# control_board.net
KiCad netlist of a schematic drawn in EAGLE
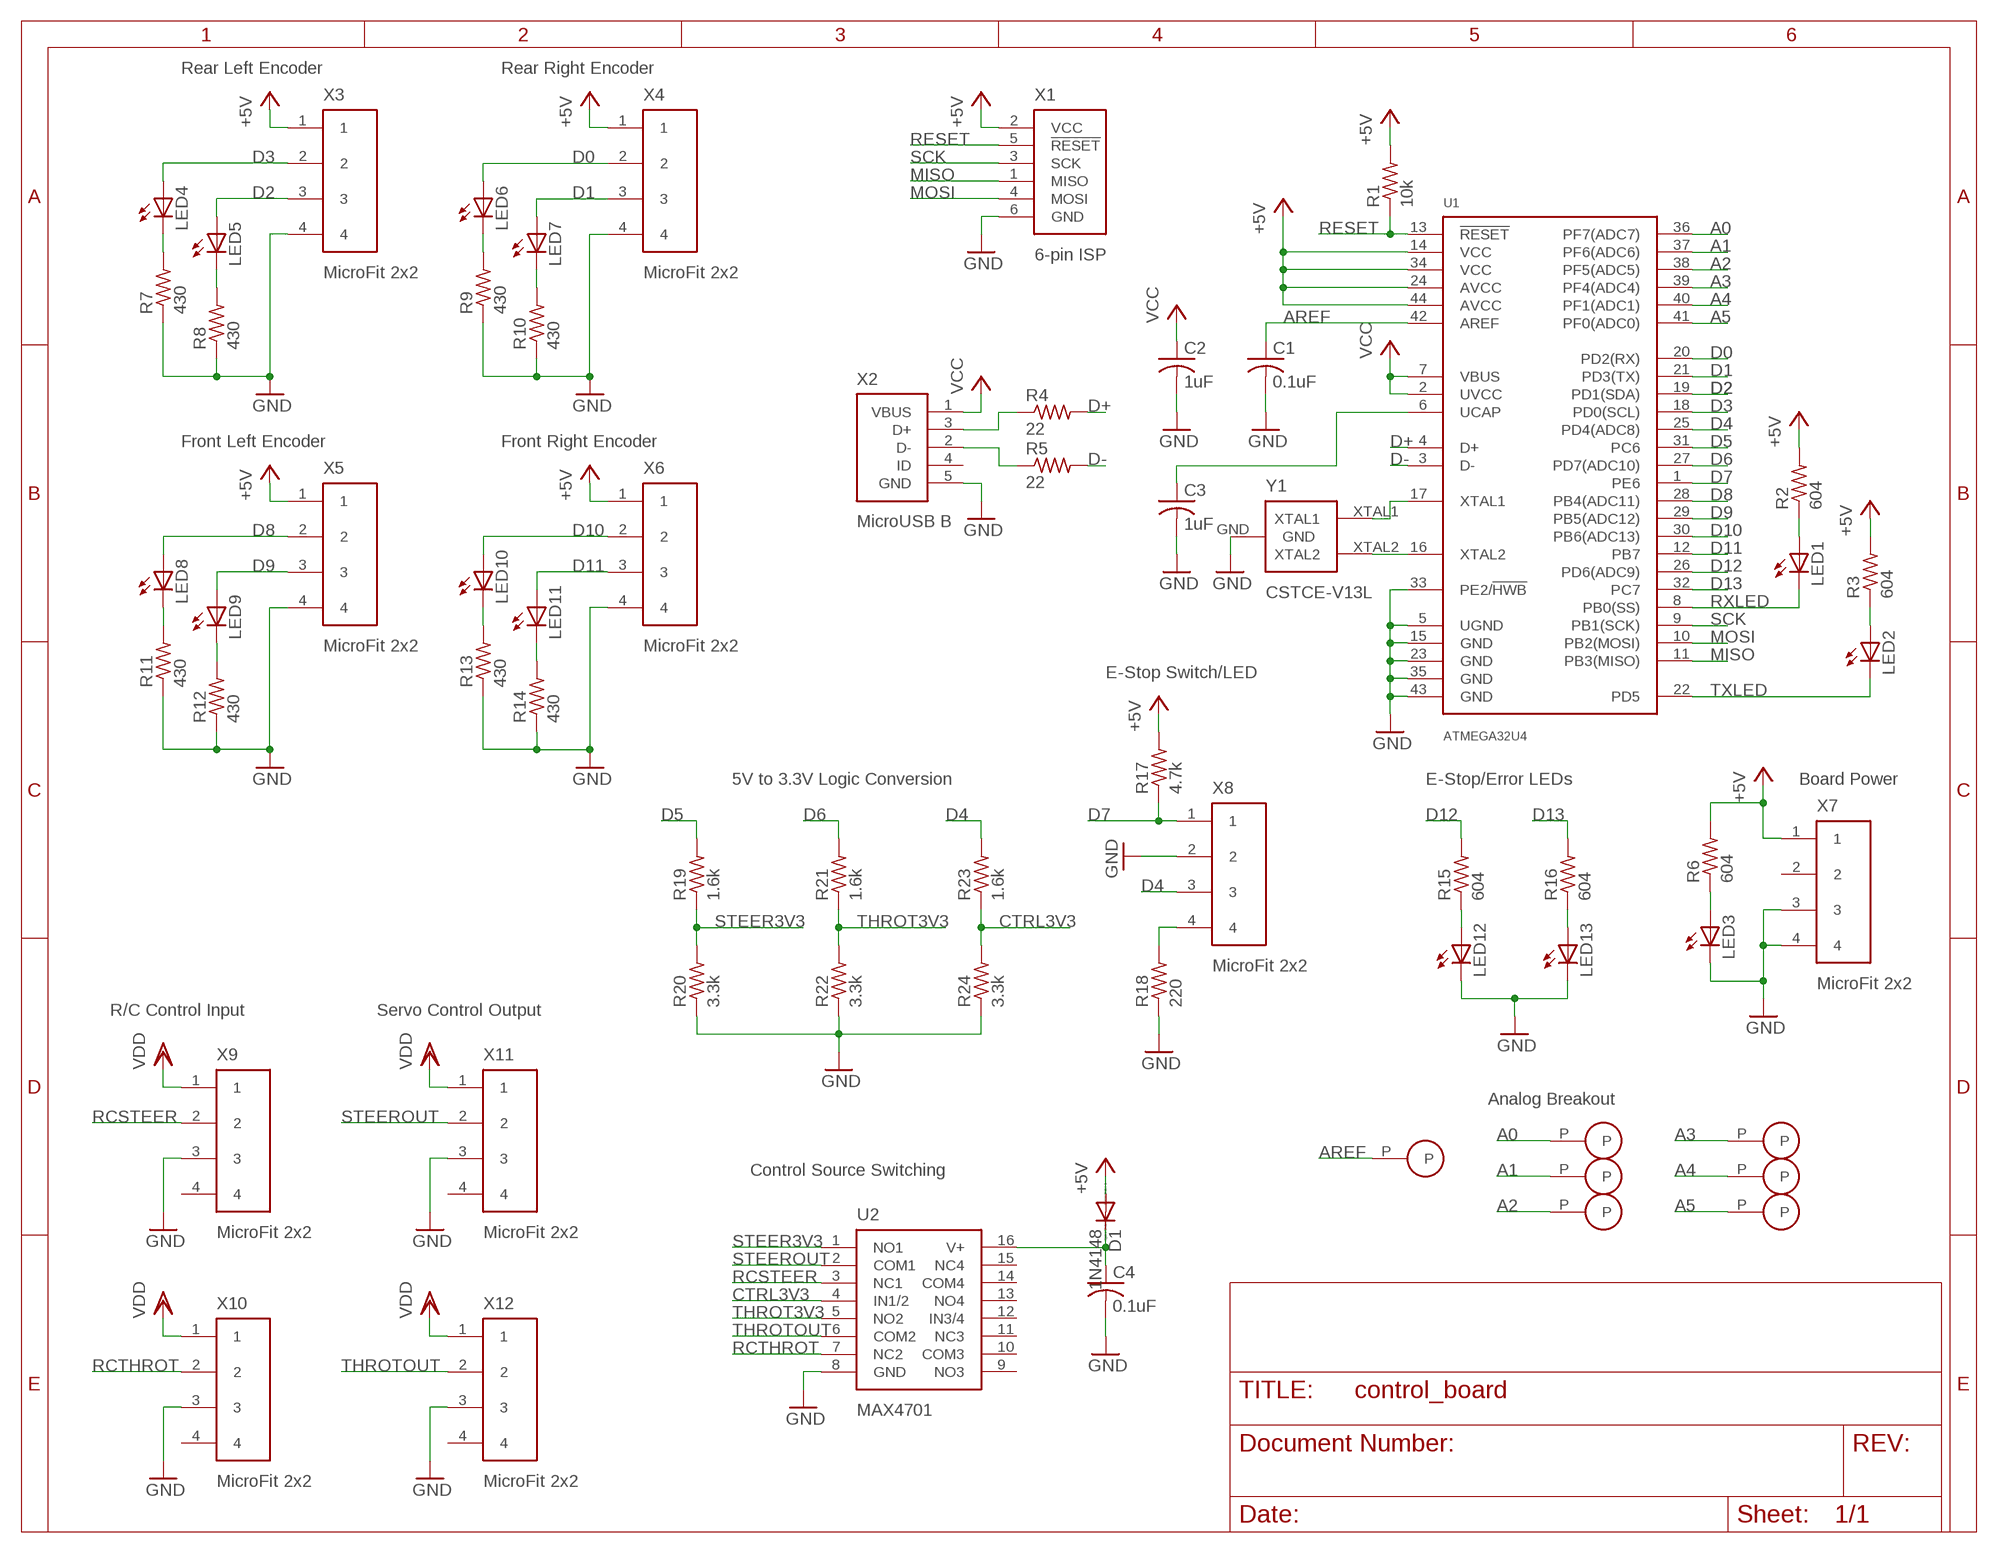
[diagram p0: schematic, sheet 1]

(export (version "E")
  (design (tool "Eeschema 10.0.6"))
  (components
    (comp (ref "C1")
      (value "0.1uF")
      (footprint "eagle-import:C0603")
      (libsource (lib "eagle-import") (part "C-USC0603"))
    )
    (comp (ref "C2")
      (value "1uF")
      (footprint "eagle-import:C0603")
      (libsource (lib "eagle-import") (part "C-USC0603"))
    )
    (comp (ref "C3")
      (value "1uF")
      (footprint "eagle-import:C0603")
      (libsource (lib "eagle-import") (part "C-USC0603"))
    )
    (comp (ref "C4")
      (value "0.1uF")
      (footprint "eagle-import:C0603")
      (libsource (lib "eagle-import") (part "C-USC0603"))
    )
    (comp (ref "D1")
      (value "1N4148")
      (footprint "eagle-import:SOD123")
      (libsource (lib "eagle-import") (part "DIODE-SOD123"))
    )
    (comp (ref "LED1")
      (value "LEDCHIPLED_0603")
      (footprint "eagle-import:CHIPLED_0603")
      (libsource (lib "eagle-import") (part "LEDCHIPLED_0603"))
    )
    (comp (ref "LED2")
      (value "LEDCHIPLED_0603")
      (footprint "eagle-import:CHIPLED_0603")
      (libsource (lib "eagle-import") (part "LEDCHIPLED_0603"))
    )
    (comp (ref "LED3")
      (value "LEDCHIPLED_0603")
      (footprint "eagle-import:CHIPLED_0603")
      (libsource (lib "eagle-import") (part "LEDCHIPLED_0603"))
    )
    (comp (ref "LED4")
      (value "LEDCHIPLED_0603")
      (footprint "eagle-import:CHIPLED_0603")
      (libsource (lib "eagle-import") (part "LEDCHIPLED_0603"))
    )
    (comp (ref "LED5")
      (value "LEDCHIPLED_0603")
      (footprint "eagle-import:CHIPLED_0603")
      (libsource (lib "eagle-import") (part "LEDCHIPLED_0603"))
    )
    (comp (ref "LED6")
      (value "LEDCHIPLED_0603")
      (footprint "eagle-import:CHIPLED_0603")
      (libsource (lib "eagle-import") (part "LEDCHIPLED_0603"))
    )
    (comp (ref "LED7")
      (value "LEDCHIPLED_0603")
      (footprint "eagle-import:CHIPLED_0603")
      (libsource (lib "eagle-import") (part "LEDCHIPLED_0603"))
    )
    (comp (ref "LED8")
      (value "LEDCHIPLED_0603")
      (footprint "eagle-import:CHIPLED_0603")
      (libsource (lib "eagle-import") (part "LEDCHIPLED_0603"))
    )
    (comp (ref "LED9")
      (value "LEDCHIPLED_0603")
      (footprint "eagle-import:CHIPLED_0603")
      (libsource (lib "eagle-import") (part "LEDCHIPLED_0603"))
    )
    (comp (ref "LED10")
      (value "LEDCHIPLED_0603")
      (footprint "eagle-import:CHIPLED_0603")
      (libsource (lib "eagle-import") (part "LEDCHIPLED_0603"))
    )
    (comp (ref "LED11")
      (value "LEDCHIPLED_0603")
      (footprint "eagle-import:CHIPLED_0603")
      (libsource (lib "eagle-import") (part "LEDCHIPLED_0603"))
    )
    (comp (ref "LED12")
      (value "LEDCHIPLED_0603")
      (footprint "eagle-import:CHIPLED_0603")
      (libsource (lib "eagle-import") (part "LEDCHIPLED_0603"))
    )
    (comp (ref "LED13")
      (value "LEDCHIPLED_0603")
      (footprint "eagle-import:CHIPLED_0603")
      (libsource (lib "eagle-import") (part "LEDCHIPLED_0603"))
    )
    (comp (ref "P1")
      (value "100MIL-PAD")
      (footprint "eagle-import:100MIL-PAD")
      (libsource (lib "eagle-import") (part "100MIL-PAD"))
    )
    (comp (ref "P2")
      (value "100MIL-PAD")
      (footprint "eagle-import:100MIL-PAD")
      (libsource (lib "eagle-import") (part "100MIL-PAD"))
    )
    (comp (ref "P3")
      (value "100MIL-PAD")
      (footprint "eagle-import:100MIL-PAD")
      (libsource (lib "eagle-import") (part "100MIL-PAD"))
    )
    (comp (ref "P4")
      (value "100MIL-PAD")
      (footprint "eagle-import:100MIL-PAD")
      (libsource (lib "eagle-import") (part "100MIL-PAD"))
    )
    (comp (ref "P5")
      (value "100MIL-PAD")
      (footprint "eagle-import:100MIL-PAD")
      (libsource (lib "eagle-import") (part "100MIL-PAD"))
    )
    (comp (ref "P6")
      (value "100MIL-PAD")
      (footprint "eagle-import:100MIL-PAD")
      (libsource (lib "eagle-import") (part "100MIL-PAD"))
    )
    (comp (ref "P7")
      (value "100MIL-PAD")
      (footprint "eagle-import:100MIL-PAD")
      (libsource (lib "eagle-import") (part "100MIL-PAD"))
    )
    (comp (ref "R1")
      (value "10k")
      (footprint "eagle-import:R0603")
      (libsource (lib "eagle-import") (part "R-US_R0603"))
    )
    (comp (ref "R2")
      (value "604")
      (footprint "eagle-import:R0603")
      (libsource (lib "eagle-import") (part "R-US_R0603"))
    )
    (comp (ref "R3")
      (value "604")
      (footprint "eagle-import:R0603")
      (libsource (lib "eagle-import") (part "R-US_R0603"))
    )
    (comp (ref "R4")
      (value "22")
      (footprint "eagle-import:R0603")
      (libsource (lib "eagle-import") (part "R-US_R0603"))
    )
    (comp (ref "R5")
      (value "22")
      (footprint "eagle-import:R0603")
      (libsource (lib "eagle-import") (part "R-US_R0603"))
    )
    (comp (ref "R6")
      (value "604")
      (footprint "eagle-import:R0603")
      (libsource (lib "eagle-import") (part "R-US_R0603"))
    )
    (comp (ref "R7")
      (value "430")
      (footprint "eagle-import:R0603")
      (libsource (lib "eagle-import") (part "R-US_R0603"))
    )
    (comp (ref "R8")
      (value "430")
      (footprint "eagle-import:R0603")
      (libsource (lib "eagle-import") (part "R-US_R0603"))
    )
    (comp (ref "R9")
      (value "430")
      (footprint "eagle-import:R0603")
      (libsource (lib "eagle-import") (part "R-US_R0603"))
    )
    (comp (ref "R10")
      (value "430")
      (footprint "eagle-import:R0603")
      (libsource (lib "eagle-import") (part "R-US_R0603"))
    )
    (comp (ref "R11")
      (value "430")
      (footprint "eagle-import:R0603")
      (libsource (lib "eagle-import") (part "R-US_R0603"))
    )
    (comp (ref "R12")
      (value "430")
      (footprint "eagle-import:R0603")
      (libsource (lib "eagle-import") (part "R-US_R0603"))
    )
    (comp (ref "R13")
      (value "430")
      (footprint "eagle-import:R0603")
      (libsource (lib "eagle-import") (part "R-US_R0603"))
    )
    (comp (ref "R14")
      (value "430")
      (footprint "eagle-import:R0603")
      (libsource (lib "eagle-import") (part "R-US_R0603"))
    )
    (comp (ref "R15")
      (value "604")
      (footprint "eagle-import:R0603")
      (libsource (lib "eagle-import") (part "R-US_R0603"))
    )
    (comp (ref "R16")
      (value "604")
      (footprint "eagle-import:R0603")
      (libsource (lib "eagle-import") (part "R-US_R0603"))
    )
    (comp (ref "R17")
      (value "4.7k")
      (footprint "eagle-import:R0603")
      (libsource (lib "eagle-import") (part "R-US_R0603"))
    )
    (comp (ref "R18")
      (value "220")
      (footprint "eagle-import:R0603")
      (libsource (lib "eagle-import") (part "R-US_R0603"))
    )
    (comp (ref "R19")
      (value "1.6k")
      (footprint "eagle-import:R0603")
      (libsource (lib "eagle-import") (part "R-US_R0603"))
    )
    (comp (ref "R20")
      (value "3.3k")
      (footprint "eagle-import:R0603")
      (libsource (lib "eagle-import") (part "R-US_R0603"))
    )
    (comp (ref "R21")
      (value "1.6k")
      (footprint "eagle-import:R0603")
      (libsource (lib "eagle-import") (part "R-US_R0603"))
    )
    (comp (ref "R22")
      (value "3.3k")
      (footprint "eagle-import:R0603")
      (libsource (lib "eagle-import") (part "R-US_R0603"))
    )
    (comp (ref "R23")
      (value "1.6k")
      (footprint "eagle-import:R0603")
      (libsource (lib "eagle-import") (part "R-US_R0603"))
    )
    (comp (ref "R24")
      (value "3.3k")
      (footprint "eagle-import:R0603")
      (libsource (lib "eagle-import") (part "R-US_R0603"))
    )
    (comp (ref "U1")
      (value "ATMEGA32U4")
      (footprint "eagle-import:TQFP-44")
      (libsource (lib "eagle-import") (part "ATMEGA32U4"))
    )
    (comp (ref "U2")
      (value "MAX4701")
      (footprint "eagle-import:TSSOP-16")
      (libsource (lib "eagle-import") (part "MAX4701"))
    )
    (comp (ref "X1")
      (value "ISP-HEADER")
      (footprint "eagle-import:ISP-HEADER")
      (libsource (lib "eagle-import") (part "ISP-HEADER"))
    )
    (comp (ref "X2")
      (value "MICRO-USB-B")
      (footprint "eagle-import:MICRO-USB-B")
      (libsource (lib "eagle-import") (part "MICRO-USB-B"))
    )
    (comp (ref "X3")
      (value "MICROFIT-2X2-SMD")
      (footprint "eagle-import:MICROFIT-2X2-0430450411")
      (libsource (lib "eagle-import") (part "MICROFIT-2X2-SMD"))
    )
    (comp (ref "X4")
      (value "MICROFIT-2X2-SMD")
      (footprint "eagle-import:MICROFIT-2X2-0430450411")
      (libsource (lib "eagle-import") (part "MICROFIT-2X2-SMD"))
    )
    (comp (ref "X5")
      (value "MICROFIT-2X2-SMD")
      (footprint "eagle-import:MICROFIT-2X2-0430450411")
      (libsource (lib "eagle-import") (part "MICROFIT-2X2-SMD"))
    )
    (comp (ref "X6")
      (value "MICROFIT-2X2-SMD")
      (footprint "eagle-import:MICROFIT-2X2-0430450411")
      (libsource (lib "eagle-import") (part "MICROFIT-2X2-SMD"))
    )
    (comp (ref "X7")
      (value "MICROFIT-2X2-SMD")
      (footprint "eagle-import:MICROFIT-2X2-0430450411")
      (libsource (lib "eagle-import") (part "MICROFIT-2X2-SMD"))
    )
    (comp (ref "X8")
      (value "MICROFIT-2X2-SMD")
      (footprint "eagle-import:MICROFIT-2X2-0430450411")
      (libsource (lib "eagle-import") (part "MICROFIT-2X2-SMD"))
    )
    (comp (ref "X9")
      (value "MICROFIT-2X2-SMD")
      (footprint "eagle-import:MICROFIT-2X2-0430450411")
      (libsource (lib "eagle-import") (part "MICROFIT-2X2-SMD"))
    )
    (comp (ref "X10")
      (value "MICROFIT-2X2-SMD")
      (footprint "eagle-import:MICROFIT-2X2-0430450411")
      (libsource (lib "eagle-import") (part "MICROFIT-2X2-SMD"))
    )
    (comp (ref "X11")
      (value "MICROFIT-2X2-SMD")
      (footprint "eagle-import:MICROFIT-2X2-0430450411")
      (libsource (lib "eagle-import") (part "MICROFIT-2X2-SMD"))
    )
    (comp (ref "X12")
      (value "MICROFIT-2X2-SMD")
      (footprint "eagle-import:MICROFIT-2X2-0430450411")
      (libsource (lib "eagle-import") (part "MICROFIT-2X2-SMD"))
    )
    (comp (ref "Y1")
      (value "CSTCE-V13L")
      (footprint "eagle-import:CSTCE-V13L")
      (libsource (lib "eagle-import") (part "CSTCE-V13L"))
    )
  )
  (nets
    (net (code "1") (name "+5V") (class "Default")
      (node (ref "D1") (pin "A") (pinfunction "A_A") (pintype "passive"))
      (node (ref "R1") (pin "2") (pinfunction "2_2") (pintype "passive"))
      (node (ref "R17") (pin "2") (pinfunction "2_2") (pintype "passive"))
      (node (ref "R2") (pin "2") (pinfunction "2_2") (pintype "passive"))
      (node (ref "R3") (pin "2") (pinfunction "2_2") (pintype "passive"))
      (node (ref "R6") (pin "2") (pinfunction "2_2") (pintype "passive"))
      (node (ref "U1") (pin "14") (pinfunction "VCC_14") (pintype "power_in"))
      (node (ref "U1") (pin "24") (pinfunction "AVCC_24") (pintype "power_in"))
      (node (ref "U1") (pin "34") (pinfunction "VCC_34") (pintype "power_in"))
      (node (ref "U1") (pin "44") (pinfunction "AVCC_44") (pintype "power_in"))
      (node (ref "X1") (pin "2") (pinfunction "VCC_2") (pintype "power_in"))
      (node (ref "X3") (pin "1") (pinfunction "1_1") (pintype "bidirectional"))
      (node (ref "X4") (pin "1") (pinfunction "1_1") (pintype "bidirectional"))
      (node (ref "X5") (pin "1") (pinfunction "1_1") (pintype "bidirectional"))
      (node (ref "X6") (pin "1") (pinfunction "1_1") (pintype "bidirectional"))
      (node (ref "X7") (pin "1") (pinfunction "1_1") (pintype "bidirectional"))
    )
    (net (code "2") (name "/A0") (class "Default")
      (node (ref "P2") (pin "P") (pinfunction "P_P") (pintype "bidirectional"))
      (node (ref "U1") (pin "36") (pinfunction "PF7(ADC7)_36") (pintype "bidirectional"))
    )
    (net (code "3") (name "/A1") (class "Default")
      (node (ref "P3") (pin "P") (pinfunction "P_P") (pintype "bidirectional"))
      (node (ref "U1") (pin "37") (pinfunction "PF6(ADC6)_37") (pintype "bidirectional"))
    )
    (net (code "4") (name "/A2") (class "Default")
      (node (ref "P4") (pin "P") (pinfunction "P_P") (pintype "bidirectional"))
      (node (ref "U1") (pin "38") (pinfunction "PF5(ADC5)_38") (pintype "bidirectional"))
    )
    (net (code "5") (name "/A3") (class "Default")
      (node (ref "P5") (pin "P") (pinfunction "P_P") (pintype "bidirectional"))
      (node (ref "U1") (pin "39") (pinfunction "PF4(ADC4)_39") (pintype "bidirectional"))
    )
    (net (code "6") (name "/A4") (class "Default")
      (node (ref "P6") (pin "P") (pinfunction "P_P") (pintype "bidirectional"))
      (node (ref "U1") (pin "40") (pinfunction "PF1(ADC1)_40") (pintype "bidirectional"))
    )
    (net (code "7") (name "/A5") (class "Default")
      (node (ref "P7") (pin "P") (pinfunction "P_P") (pintype "bidirectional"))
      (node (ref "U1") (pin "41") (pinfunction "PF0(ADC0)_41") (pintype "bidirectional"))
    )
    (net (code "8") (name "/AREF") (class "Default")
      (node (ref "C1") (pin "1") (pinfunction "1_1") (pintype "passive"))
      (node (ref "P1") (pin "P") (pinfunction "P_P") (pintype "bidirectional"))
      (node (ref "U1") (pin "42") (pinfunction "AREF_42") (pintype "input"))
    )
    (net (code "9") (name "/CTRL3V3") (class "Default")
      (node (ref "R23") (pin "1") (pinfunction "1_1") (pintype "passive"))
      (node (ref "R24") (pin "2") (pinfunction "2_2") (pintype "passive"))
      (node (ref "U2") (pin "4") (pinfunction "IN1/2_4") (pintype "bidirectional"))
    )
    (net (code "10") (name "/D+") (class "Default")
      (node (ref "R4") (pin "2") (pinfunction "2_2") (pintype "passive"))
      (node (ref "U1") (pin "4") (pinfunction "D+_4") (pintype "bidirectional"))
    )
    (net (code "11") (name "/D-") (class "Default")
      (node (ref "R5") (pin "2") (pinfunction "2_2") (pintype "passive"))
      (node (ref "U1") (pin "3") (pinfunction "D-_3") (pintype "bidirectional"))
    )
    (net (code "12") (name "/D0") (class "Default")
      (node (ref "LED6") (pin "A") (pinfunction "A_A") (pintype "passive"))
      (node (ref "U1") (pin "20") (pinfunction "PD2(RX)_20") (pintype "bidirectional"))
      (node (ref "X4") (pin "2") (pinfunction "2_2") (pintype "bidirectional"))
    )
    (net (code "13") (name "/D1") (class "Default")
      (node (ref "LED7") (pin "A") (pinfunction "A_A") (pintype "passive"))
      (node (ref "U1") (pin "21") (pinfunction "PD3(TX)_21") (pintype "bidirectional"))
      (node (ref "X4") (pin "3") (pinfunction "3_3") (pintype "bidirectional"))
    )
    (net (code "14") (name "/D2") (class "Default")
      (node (ref "LED5") (pin "A") (pinfunction "A_A") (pintype "passive"))
      (node (ref "U1") (pin "19") (pinfunction "PD1(SDA)_19") (pintype "bidirectional"))
      (node (ref "X3") (pin "3") (pinfunction "3_3") (pintype "bidirectional"))
    )
    (net (code "15") (name "/D3") (class "Default")
      (node (ref "LED4") (pin "A") (pinfunction "A_A") (pintype "passive"))
      (node (ref "U1") (pin "18") (pinfunction "PD0(SCL)_18") (pintype "bidirectional"))
      (node (ref "X3") (pin "2") (pinfunction "2_2") (pintype "bidirectional"))
    )
    (net (code "16") (name "/D4") (class "Default")
      (node (ref "R23") (pin "2") (pinfunction "2_2") (pintype "passive"))
      (node (ref "U1") (pin "25") (pinfunction "PD4(ADC8)_25") (pintype "bidirectional"))
      (node (ref "X8") (pin "3") (pinfunction "3_3") (pintype "bidirectional"))
    )
    (net (code "17") (name "/D5") (class "Default")
      (node (ref "R19") (pin "2") (pinfunction "2_2") (pintype "passive"))
      (node (ref "U1") (pin "31") (pinfunction "PC6_31") (pintype "bidirectional"))
    )
    (net (code "18") (name "/D6") (class "Default")
      (node (ref "R21") (pin "2") (pinfunction "2_2") (pintype "passive"))
      (node (ref "U1") (pin "27") (pinfunction "PD7(ADC10)_27") (pintype "bidirectional"))
    )
    (net (code "19") (name "/D7") (class "Default")
      (node (ref "R17") (pin "1") (pinfunction "1_1") (pintype "passive"))
      (node (ref "U1") (pin "1") (pinfunction "PE6_1") (pintype "bidirectional"))
      (node (ref "X8") (pin "1") (pinfunction "1_1") (pintype "bidirectional"))
    )
    (net (code "20") (name "/D8") (class "Default")
      (node (ref "LED8") (pin "A") (pinfunction "A_A") (pintype "passive"))
      (node (ref "U1") (pin "28") (pinfunction "PB4(ADC11)_28") (pintype "bidirectional"))
      (node (ref "X5") (pin "2") (pinfunction "2_2") (pintype "bidirectional"))
    )
    (net (code "21") (name "/D9") (class "Default")
      (node (ref "LED9") (pin "A") (pinfunction "A_A") (pintype "passive"))
      (node (ref "U1") (pin "29") (pinfunction "PB5(ADC12)_29") (pintype "bidirectional"))
      (node (ref "X5") (pin "3") (pinfunction "3_3") (pintype "bidirectional"))
    )
    (net (code "22") (name "/D10") (class "Default")
      (node (ref "LED10") (pin "A") (pinfunction "A_A") (pintype "passive"))
      (node (ref "U1") (pin "30") (pinfunction "PB6(ADC13)_30") (pintype "bidirectional"))
      (node (ref "X6") (pin "2") (pinfunction "2_2") (pintype "bidirectional"))
    )
    (net (code "23") (name "/D11") (class "Default")
      (node (ref "LED11") (pin "A") (pinfunction "A_A") (pintype "passive"))
      (node (ref "U1") (pin "12") (pinfunction "PB7_12") (pintype "bidirectional"))
      (node (ref "X6") (pin "3") (pinfunction "3_3") (pintype "bidirectional"))
    )
    (net (code "24") (name "/D12") (class "Default")
      (node (ref "R15") (pin "2") (pinfunction "2_2") (pintype "passive"))
      (node (ref "U1") (pin "26") (pinfunction "PD6(ADC9)_26") (pintype "bidirectional"))
    )
    (net (code "25") (name "/D13") (class "Default")
      (node (ref "R16") (pin "2") (pinfunction "2_2") (pintype "passive"))
      (node (ref "U1") (pin "32") (pinfunction "PC7_32") (pintype "bidirectional"))
    )
    (net (code "26") (name "/MISO") (class "Default")
      (node (ref "U1") (pin "11") (pinfunction "PB3(MISO)_11") (pintype "bidirectional"))
      (node (ref "X1") (pin "1") (pinfunction "MISO_1") (pintype "bidirectional"))
    )
    (net (code "27") (name "/MOSI") (class "Default")
      (node (ref "U1") (pin "10") (pinfunction "PB2(MOSI)_10") (pintype "bidirectional"))
      (node (ref "X1") (pin "4") (pinfunction "MOSI_4") (pintype "bidirectional"))
    )
    (net (code "28") (name "/RCSTEER") (class "Default")
      (node (ref "U2") (pin "3") (pinfunction "NC1_3") (pintype "bidirectional"))
      (node (ref "X9") (pin "2") (pinfunction "2_2") (pintype "bidirectional"))
    )
    (net (code "29") (name "/RCTHROT") (class "Default")
      (node (ref "U2") (pin "7") (pinfunction "NC2_7") (pintype "bidirectional"))
      (node (ref "X10") (pin "2") (pinfunction "2_2") (pintype "bidirectional"))
    )
    (net (code "30") (name "/RESET") (class "Default")
      (node (ref "R1") (pin "1") (pinfunction "1_1") (pintype "passive"))
      (node (ref "U1") (pin "13") (pinfunction "~{RESET}_13") (pintype "input"))
      (node (ref "X1") (pin "5") (pinfunction "~{RESET}_5") (pintype "bidirectional"))
    )
    (net (code "31") (name "/RXLED") (class "Default")
      (node (ref "LED1") (pin "C") (pinfunction "C_C") (pintype "passive"))
      (node (ref "U1") (pin "8") (pinfunction "PB0(SS)_8") (pintype "bidirectional"))
    )
    (net (code "32") (name "/SCK") (class "Default")
      (node (ref "U1") (pin "9") (pinfunction "PB1(SCK)_9") (pintype "bidirectional"))
      (node (ref "X1") (pin "3") (pinfunction "SCK_3") (pintype "bidirectional"))
    )
    (net (code "33") (name "/STEER3V3") (class "Default")
      (node (ref "R19") (pin "1") (pinfunction "1_1") (pintype "passive"))
      (node (ref "R20") (pin "2") (pinfunction "2_2") (pintype "passive"))
      (node (ref "U2") (pin "1") (pinfunction "NO1_1") (pintype "bidirectional"))
    )
    (net (code "34") (name "/STEEROUT") (class "Default")
      (node (ref "U2") (pin "2") (pinfunction "COM1_2") (pintype "bidirectional"))
      (node (ref "X11") (pin "2") (pinfunction "2_2") (pintype "bidirectional"))
    )
    (net (code "35") (name "/THROT3V3") (class "Default")
      (node (ref "R21") (pin "1") (pinfunction "1_1") (pintype "passive"))
      (node (ref "R22") (pin "2") (pinfunction "2_2") (pintype "passive"))
      (node (ref "U2") (pin "5") (pinfunction "NO2_5") (pintype "bidirectional"))
    )
    (net (code "36") (name "/THROTOUT") (class "Default")
      (node (ref "U2") (pin "6") (pinfunction "COM2_6") (pintype "bidirectional"))
      (node (ref "X12") (pin "2") (pinfunction "2_2") (pintype "bidirectional"))
    )
    (net (code "37") (name "/TXLED") (class "Default")
      (node (ref "LED2") (pin "C") (pinfunction "C_C") (pintype "passive"))
      (node (ref "U1") (pin "22") (pinfunction "PD5_22") (pintype "bidirectional"))
    )
    (net (code "38") (name "GND") (class "Default")
      (node (ref "C1") (pin "2") (pinfunction "2_2") (pintype "passive"))
      (node (ref "C2") (pin "2") (pinfunction "2_2") (pintype "passive"))
      (node (ref "C3") (pin "2") (pinfunction "2_2") (pintype "passive"))
      (node (ref "C4") (pin "2") (pinfunction "2_2") (pintype "passive"))
      (node (ref "LED12") (pin "C") (pinfunction "C_C") (pintype "passive"))
      (node (ref "LED13") (pin "C") (pinfunction "C_C") (pintype "passive"))
      (node (ref "LED3") (pin "C") (pinfunction "C_C") (pintype "passive"))
      (node (ref "R10") (pin "1") (pinfunction "1_1") (pintype "passive"))
      (node (ref "R11") (pin "1") (pinfunction "1_1") (pintype "passive"))
      (node (ref "R12") (pin "1") (pinfunction "1_1") (pintype "passive"))
      (node (ref "R13") (pin "1") (pinfunction "1_1") (pintype "passive"))
      (node (ref "R14") (pin "1") (pinfunction "1_1") (pintype "passive"))
      (node (ref "R18") (pin "1") (pinfunction "1_1") (pintype "passive"))
      (node (ref "R20") (pin "1") (pinfunction "1_1") (pintype "passive"))
      (node (ref "R22") (pin "1") (pinfunction "1_1") (pintype "passive"))
      (node (ref "R24") (pin "1") (pinfunction "1_1") (pintype "passive"))
      (node (ref "R7") (pin "1") (pinfunction "1_1") (pintype "passive"))
      (node (ref "R8") (pin "1") (pinfunction "1_1") (pintype "passive"))
      (node (ref "R9") (pin "1") (pinfunction "1_1") (pintype "passive"))
      (node (ref "U1") (pin "15") (pinfunction "GND_15") (pintype "power_in"))
      (node (ref "U1") (pin "23") (pinfunction "GND_23") (pintype "power_in"))
      (node (ref "U1") (pin "33") (pinfunction "PE2/~{HWB}_33") (pintype "bidirectional"))
      (node (ref "U1") (pin "35") (pinfunction "GND_35") (pintype "power_in"))
      (node (ref "U1") (pin "43") (pinfunction "GND_43") (pintype "power_in"))
      (node (ref "U1") (pin "5") (pinfunction "UGND_5") (pintype "power_in"))
      (node (ref "U2") (pin "8") (pinfunction "GND_8") (pintype "power_in"))
      (node (ref "X1") (pin "6") (pinfunction "GND_6") (pintype "power_in"))
      (node (ref "X10") (pin "3") (pinfunction "3_3") (pintype "bidirectional"))
      (node (ref "X11") (pin "3") (pinfunction "3_3") (pintype "bidirectional"))
      (node (ref "X12") (pin "3") (pinfunction "3_3") (pintype "bidirectional"))
      (node (ref "X2") (pin "5") (pinfunction "GND_5") (pintype "power_in"))
      (node (ref "X3") (pin "4") (pinfunction "4_4") (pintype "bidirectional"))
      (node (ref "X4") (pin "4") (pinfunction "4_4") (pintype "bidirectional"))
      (node (ref "X5") (pin "4") (pinfunction "4_4") (pintype "bidirectional"))
      (node (ref "X6") (pin "4") (pinfunction "4_4") (pintype "bidirectional"))
      (node (ref "X7") (pin "3") (pinfunction "3_3") (pintype "bidirectional"))
      (node (ref "X7") (pin "4") (pinfunction "4_4") (pintype "bidirectional"))
      (node (ref "X8") (pin "2") (pinfunction "2_2") (pintype "bidirectional"))
      (node (ref "X9") (pin "3") (pinfunction "3_3") (pintype "bidirectional"))
      (node (ref "Y1") (pin "GND") (pinfunction "GND_GND") (pintype "power_in"))
    )
    (net (code "39") (name "Net-(LED1-PadA)") (class "Default")
      (node (ref "LED1") (pin "A") (pinfunction "A_A") (pintype "passive"))
      (node (ref "R2") (pin "1") (pinfunction "1_1") (pintype "passive"))
    )
    (net (code "40") (name "Net-(LED2-PadA)") (class "Default")
      (node (ref "LED2") (pin "A") (pinfunction "A_A") (pintype "passive"))
      (node (ref "R3") (pin "1") (pinfunction "1_1") (pintype "passive"))
    )
    (net (code "41") (name "Net-(LED3-PadA)") (class "Default")
      (node (ref "LED3") (pin "A") (pinfunction "A_A") (pintype "passive"))
      (node (ref "R6") (pin "1") (pinfunction "1_1") (pintype "passive"))
    )
    (net (code "42") (name "Net-(LED4-PadC)") (class "Default")
      (node (ref "LED4") (pin "C") (pinfunction "C_C") (pintype "passive"))
      (node (ref "R7") (pin "2") (pinfunction "2_2") (pintype "passive"))
    )
    (net (code "43") (name "Net-(LED5-PadC)") (class "Default")
      (node (ref "LED5") (pin "C") (pinfunction "C_C") (pintype "passive"))
      (node (ref "R8") (pin "2") (pinfunction "2_2") (pintype "passive"))
    )
    (net (code "44") (name "Net-(LED6-PadC)") (class "Default")
      (node (ref "LED6") (pin "C") (pinfunction "C_C") (pintype "passive"))
      (node (ref "R9") (pin "2") (pinfunction "2_2") (pintype "passive"))
    )
    (net (code "45") (name "Net-(LED7-PadC)") (class "Default")
      (node (ref "LED7") (pin "C") (pinfunction "C_C") (pintype "passive"))
      (node (ref "R10") (pin "2") (pinfunction "2_2") (pintype "passive"))
    )
    (net (code "46") (name "Net-(LED8-PadC)") (class "Default")
      (node (ref "LED8") (pin "C") (pinfunction "C_C") (pintype "passive"))
      (node (ref "R11") (pin "2") (pinfunction "2_2") (pintype "passive"))
    )
    (net (code "47") (name "Net-(LED9-PadC)") (class "Default")
      (node (ref "LED9") (pin "C") (pinfunction "C_C") (pintype "passive"))
      (node (ref "R12") (pin "2") (pinfunction "2_2") (pintype "passive"))
    )
    (net (code "48") (name "Net-(LED10-PadC)") (class "Default")
      (node (ref "LED10") (pin "C") (pinfunction "C_C") (pintype "passive"))
      (node (ref "R13") (pin "2") (pinfunction "2_2") (pintype "passive"))
    )
    (net (code "49") (name "Net-(LED11-PadC)") (class "Default")
      (node (ref "LED11") (pin "C") (pinfunction "C_C") (pintype "passive"))
      (node (ref "R14") (pin "2") (pinfunction "2_2") (pintype "passive"))
    )
    (net (code "50") (name "Net-(LED12-PadA)") (class "Default")
      (node (ref "LED12") (pin "A") (pinfunction "A_A") (pintype "passive"))
      (node (ref "R15") (pin "1") (pinfunction "1_1") (pintype "passive"))
    )
    (net (code "51") (name "Net-(LED13-PadA)") (class "Default")
      (node (ref "LED13") (pin "A") (pinfunction "A_A") (pintype "passive"))
      (node (ref "R16") (pin "1") (pinfunction "1_1") (pintype "passive"))
    )
    (net (code "52") (name "Net-(R18-Pad2)") (class "Default")
      (node (ref "R18") (pin "2") (pinfunction "2_2") (pintype "passive"))
      (node (ref "X8") (pin "4") (pinfunction "4_4") (pintype "bidirectional"))
    )
    (net (code "53") (name "Net-(U1-UCAP)") (class "Default")
      (node (ref "C3") (pin "1") (pinfunction "1_1") (pintype "passive"))
      (node (ref "U1") (pin "6") (pinfunction "UCAP_6") (pintype "bidirectional"))
    )
    (net (code "54") (name "Net-(U1-XTAL1)") (class "Default")
      (node (ref "U1") (pin "17") (pinfunction "XTAL1_17") (pintype "bidirectional"))
      (node (ref "Y1") (pin "XTAL1") (pinfunction "XTAL1_XTAL1") (pintype "bidirectional"))
    )
    (net (code "55") (name "Net-(U1-XTAL2)") (class "Default")
      (node (ref "U1") (pin "16") (pinfunction "XTAL2_16") (pintype "bidirectional"))
      (node (ref "Y1") (pin "XTAL2") (pinfunction "XTAL2_XTAL2") (pintype "bidirectional"))
    )
    (net (code "56") (name "Net-(U2-V+)") (class "Default")
      (node (ref "C4") (pin "1") (pinfunction "1_1") (pintype "passive"))
      (node (ref "D1") (pin "C") (pinfunction "C_C") (pintype "passive"))
      (node (ref "U2") (pin "16") (pinfunction "V+_16") (pintype "power_in"))
    )
    (net (code "57") (name "Net-(X2-D+)") (class "Default")
      (node (ref "R4") (pin "1") (pinfunction "1_1") (pintype "passive"))
      (node (ref "X2") (pin "3") (pinfunction "D+_3") (pintype "bidirectional"))
    )
    (net (code "58") (name "Net-(X2-D-)") (class "Default")
      (node (ref "R5") (pin "1") (pinfunction "1_1") (pintype "passive"))
      (node (ref "X2") (pin "2") (pinfunction "D-_2") (pintype "bidirectional"))
    )
    (net (code "59") (name "VCC") (class "Default")
      (node (ref "C2") (pin "1") (pinfunction "1_1") (pintype "passive"))
      (node (ref "U1") (pin "2") (pinfunction "UVCC_2") (pintype "power_in"))
      (node (ref "U1") (pin "7") (pinfunction "VBUS_7") (pintype "power_in"))
      (node (ref "X2") (pin "1") (pinfunction "VBUS_1") (pintype "power_in"))
    )
    (net (code "60") (name "VDD") (class "Default")
      (node (ref "X10") (pin "1") (pinfunction "1_1") (pintype "bidirectional"))
      (node (ref "X11") (pin "1") (pinfunction "1_1") (pintype "bidirectional"))
      (node (ref "X12") (pin "1") (pinfunction "1_1") (pintype "bidirectional"))
      (node (ref "X9") (pin "1") (pinfunction "1_1") (pintype "bidirectional"))
    )
    (net (code "61") (name "unconnected-(U2-COM3-Pad10)") (class "Default")
      (node (ref "U2") (pin "10") (pinfunction "COM3_10") (pintype "bidirectional"))
    )
    (net (code "62") (name "unconnected-(U2-COM4-Pad14)") (class "Default")
      (node (ref "U2") (pin "14") (pinfunction "COM4_14") (pintype "bidirectional"))
    )
    (net (code "63") (name "unconnected-(U2-IN3{slash}4-Pad12)") (class "Default")
      (node (ref "U2") (pin "12") (pinfunction "IN3/4_12") (pintype "bidirectional"))
    )
    (net (code "64") (name "unconnected-(U2-NC3-Pad11)") (class "Default")
      (node (ref "U2") (pin "11") (pinfunction "NC3_11") (pintype "bidirectional"))
    )
    (net (code "65") (name "unconnected-(U2-NC4-Pad15)") (class "Default")
      (node (ref "U2") (pin "15") (pinfunction "NC4_15") (pintype "bidirectional"))
    )
    (net (code "66") (name "unconnected-(U2-NO3-Pad9)") (class "Default")
      (node (ref "U2") (pin "9") (pinfunction "NO3_9") (pintype "bidirectional"))
    )
    (net (code "67") (name "unconnected-(U2-NO4-Pad13)") (class "Default")
      (node (ref "U2") (pin "13") (pinfunction "NO4_13") (pintype "bidirectional"))
    )
    (net (code "68") (name "unconnected-(X2-ID-Pad4)") (class "Default")
      (node (ref "X2") (pin "4") (pinfunction "ID_4") (pintype "bidirectional"))
    )
    (net (code "69") (name "unconnected-(X7-Pad2)") (class "Default")
      (node (ref "X7") (pin "2") (pinfunction "2_2") (pintype "bidirectional"))
    )
    (net (code "70") (name "unconnected-(X9-Pad4)") (class "Default")
      (node (ref "X9") (pin "4") (pinfunction "4_4") (pintype "bidirectional"))
    )
    (net (code "71") (name "unconnected-(X10-Pad4)") (class "Default")
      (node (ref "X10") (pin "4") (pinfunction "4_4") (pintype "bidirectional"))
    )
    (net (code "72") (name "unconnected-(X11-Pad4)") (class "Default")
      (node (ref "X11") (pin "4") (pinfunction "4_4") (pintype "bidirectional"))
    )
    (net (code "73") (name "unconnected-(X12-Pad4)") (class "Default")
      (node (ref "X12") (pin "4") (pinfunction "4_4") (pintype "bidirectional"))
    )
  )
)
